# SCH_RESETDAY.net
KiCad netlist of a schematic drawn in Altium Designer
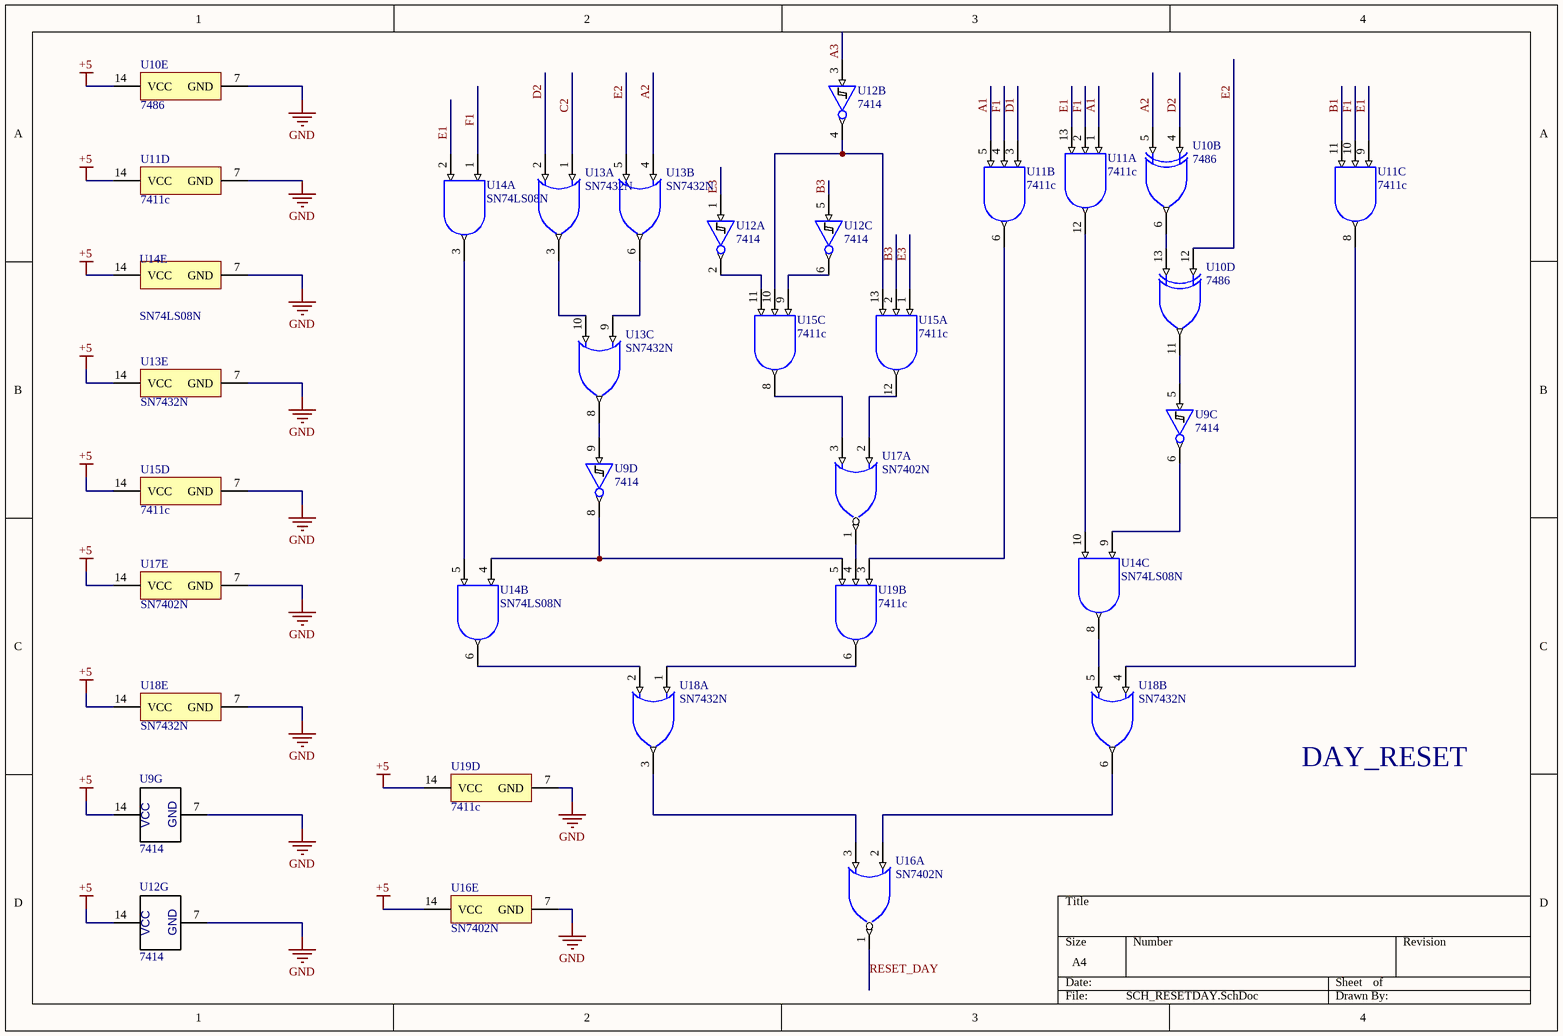
[diagram p0: SCH_RESETDAY.SchDoc]

(export (version "E")
  (design (tool "Eeschema 10.0.6"))
  (components
    (comp (ref "U9")
      (value "7414")
      (footprint "DIP14")
      (description "IC, M74HC04M, Hex Inverter, SO-14")
      (libsource (lib "") (part "7414_1"))
    )
    (comp (ref "U10")
      (value "7486")
      (footprint "N0014A")
      (description "High Speed CMOS Logic Quad 2-Input Exclusive-OR Gates, N0014A, TUBE")
      (fields
        (field (name "MANUFACTURER") "Texas Instruments")
        (field (name "GENERIC PART NUMBER") "CD74HC86")
      )
      (libsource (lib "Clock_Schlib1") (part "7486"))
    )
    (comp (ref "U11")
      (value "7411c")
      (footprint "N0014A")
      (description "High Speed CMOS Logic Triple 3-Input AND Gates, N0014A, TUBE")
      (fields
        (field (name "GENERIC PART NUMBER") "CD74HC11")
        (field (name "MANUFACTURER") "Texas Instruments")
      )
      (libsource (lib "") (part "7411c_1"))
    )
    (comp (ref "U12")
      (value "7414")
      (footprint "DIP14")
      (description "IC, M74HC04M, Hex Inverter, SO-14")
      (libsource (lib "") (part "7414_3"))
    )
    (comp (ref "U13")
      (value "SN7432N")
      (footprint "N0014A")
      (description "Quad 2-input positive-OR gates, N0014A, TUBE")
      (fields (field (name "MANUFACTURER") "Texas Instruments") (field (name "GENERIC PART NUMBER") "SN7432"))
      (libsource (lib "Altium Content Vault") (part "TI-OR-4-2IN-14"))
    )
    (comp (ref "U14")
      (value "SN74LS08N")
      (footprint "N0014A")
      (description "Quadruple 2-Input Positive-AND Gates, N0014A, TUBE")
      (fields
        (field (name "MANUFACTURER") "Texas Instruments")
        (field (name "GENERIC PART NUMBER") "SN74LS08")
      )
      (libsource (lib "") (part "TI-AND-4-2IN-14_1"))
    )
    (comp (ref "U15")
      (value "7411c")
      (footprint "N0014A")
      (description "High Speed CMOS Logic Triple 3-Input AND Gates, N0014A, TUBE")
      (fields
        (field (name "GENERIC PART NUMBER") "CD74HC11")
        (field (name "MANUFACTURER") "Texas Instruments")
      )
      (libsource (lib "Clock_Schlib1") (part "7411c"))
    )
    (comp (ref "U16")
      (value "SN7402N")
      (footprint "N0014A")
      (description "Quad 2-input Positive-NOR gates, N0014A, TUBE")
      (fields (field (name "GENERIC PART NUMBER") "SN7402") (field (name "MANUFACTURER") "Texas Instruments"))
      (libsource (lib "") (part "TI-NOR-4-2IN-14_1"))
    )
    (comp (ref "U17")
      (value "SN7402N")
      (footprint "N0014A")
      (description "Quad 2-input Positive-NOR gates, N0014A, TUBE")
      (fields (field (name "GENERIC PART NUMBER") "SN7402") (field (name "MANUFACTURER") "Texas Instruments"))
      (libsource (lib "Altium Content Vault") (part "TI-NOR-4-2IN-14"))
    )
    (comp (ref "U18")
      (value "SN7432N")
      (footprint "N0014A")
      (description "Quad 2-input positive-OR gates, N0014A, TUBE")
      (fields (field (name "MANUFACTURER") "Texas Instruments") (field (name "GENERIC PART NUMBER") "SN7432"))
      (libsource (lib "") (part "TI-OR-4-2IN-14_1"))
    )
    (comp (ref "U19")
      (value "7411c")
      (footprint "N0014A")
      (description "High Speed CMOS Logic Triple 3-Input AND Gates, N0014A, TUBE")
      (fields
        (field (name "GENERIC PART NUMBER") "CD74HC11")
        (field (name "MANUFACTURER") "Texas Instruments")
      )
      (libsource (lib "Clock_Schlib1") (part "7411c"))
    )
  )
  (nets
    (net (code "1") (name "+5") (class "Default")
      (node (ref "U10") (pin "14") (pinfunction "VCC_14") (pintype "power_in"))
      (node (ref "U11") (pin "14") (pinfunction "VCC_14") (pintype "power_in"))
      (node (ref "U12") (pin "14") (pinfunction "VCC_14") (pintype "passive"))
      (node (ref "U13") (pin "14") (pinfunction "VCC_14") (pintype "power_in"))
      (node (ref "U14") (pin "14") (pinfunction "VCC_14") (pintype "power_in"))
      (node (ref "U15") (pin "14") (pinfunction "VCC_14") (pintype "power_in"))
      (node (ref "U16") (pin "14") (pinfunction "VCC_14") (pintype "power_in"))
      (node (ref "U17") (pin "14") (pinfunction "VCC_14") (pintype "power_in"))
      (node (ref "U18") (pin "14") (pinfunction "VCC_14") (pintype "power_in"))
      (node (ref "U19") (pin "14") (pinfunction "VCC_14") (pintype "power_in"))
      (node (ref "U9") (pin "14") (pinfunction "VCC_14") (pintype "passive"))
    )
    (net (code "2") (name "/A1") (class "Default")
      (node (ref "U11") (pin "1") (pinfunction "1A_1") (pintype "input"))
      (node (ref "U11") (pin "5") (pinfunction "2C_5") (pintype "input"))
    )
    (net (code "3") (name "/A2") (class "Default")
      (node (ref "U10") (pin "5") (pinfunction "2B_5") (pintype "input"))
      (node (ref "U13") (pin "4") (pinfunction "2A_4") (pintype "input"))
    )
    (net (code "4") (name "/A3") (class "Default")
      (node (ref "U12") (pin "3") (pinfunction "A_3") (pintype "input"))
    )
    (net (code "5") (name "/B1") (class "Default")
      (node (ref "U11") (pin "11") (pinfunction "3C_11") (pintype "input"))
    )
    (net (code "6") (name "/B3") (class "Default")
      (node (ref "U12") (pin "5") (pinfunction "A_5") (pintype "input"))
      (node (ref "U15") (pin "2") (pinfunction "1B_2") (pintype "input"))
    )
    (net (code "7") (name "/C2") (class "Default")
      (node (ref "U13") (pin "1") (pinfunction "1A_1") (pintype "input"))
    )
    (net (code "8") (name "/D1") (class "Default")
      (node (ref "U11") (pin "3") (pinfunction "2A_3") (pintype "input"))
    )
    (net (code "9") (name "/D2") (class "Default")
      (node (ref "U10") (pin "4") (pinfunction "2A_4") (pintype "input"))
      (node (ref "U13") (pin "2") (pinfunction "1B_2") (pintype "input"))
    )
    (net (code "10") (name "/E1") (class "Default")
      (node (ref "U11") (pin "13") (pinfunction "1C_13") (pintype "input"))
      (node (ref "U11") (pin "9") (pinfunction "3A_9") (pintype "input"))
      (node (ref "U14") (pin "2") (pinfunction "1B_2") (pintype "input"))
    )
    (net (code "11") (name "/E2") (class "Default")
      (node (ref "U10") (pin "12") (pinfunction "4A_12") (pintype "input"))
      (node (ref "U13") (pin "5") (pinfunction "2B_5") (pintype "input"))
    )
    (net (code "12") (name "/E3") (class "Default")
      (node (ref "U12") (pin "1") (pinfunction "A_1") (pintype "input"))
      (node (ref "U15") (pin "1") (pinfunction "1A_1") (pintype "input"))
    )
    (net (code "13") (name "/F1") (class "Default")
      (node (ref "U11") (pin "10") (pinfunction "3B_10") (pintype "input"))
      (node (ref "U11") (pin "2") (pinfunction "1B_2") (pintype "input"))
      (node (ref "U11") (pin "4") (pinfunction "2B_4") (pintype "input"))
      (node (ref "U14") (pin "1") (pinfunction "1A_1") (pintype "input"))
    )
    (net (code "14") (name "/RESET_DAY") (class "Default")
      (node (ref "U16") (pin "1") (pinfunction "1Y_1") (pintype "output"))
    )
    (net (code "15") (name "GND") (class "Default")
      (node (ref "U10") (pin "7") (pinfunction "GND_7") (pintype "power_in"))
      (node (ref "U11") (pin "7") (pinfunction "GND_7") (pintype "power_in"))
      (node (ref "U12") (pin "7") (pinfunction "GND_7") (pintype "passive"))
      (node (ref "U13") (pin "7") (pinfunction "GND_7") (pintype "power_in"))
      (node (ref "U14") (pin "7") (pinfunction "GND_7") (pintype "power_in"))
      (node (ref "U15") (pin "7") (pinfunction "GND_7") (pintype "power_in"))
      (node (ref "U16") (pin "7") (pinfunction "GND_7") (pintype "power_in"))
      (node (ref "U17") (pin "7") (pinfunction "GND_7") (pintype "power_in"))
      (node (ref "U18") (pin "7") (pinfunction "GND_7") (pintype "power_in"))
      (node (ref "U19") (pin "7") (pinfunction "GND_7") (pintype "power_in"))
      (node (ref "U9") (pin "7") (pinfunction "GND_7") (pintype "passive"))
    )
    (net (code "16") (name "Net-(U10B-2Y)") (class "Default")
      (node (ref "U10") (pin "13") (pinfunction "4B_13") (pintype "input"))
      (node (ref "U10") (pin "6") (pinfunction "2Y_6") (pintype "output"))
    )
    (net (code "17") (name "Net-(U10D-4Y)") (class "Default")
      (node (ref "U10") (pin "11") (pinfunction "4Y_11") (pintype "output"))
      (node (ref "U9") (pin "5") (pinfunction "A_5") (pintype "input"))
    )
    (net (code "18") (name "Net-(U11A-1Y)") (class "Default")
      (node (ref "U11") (pin "12") (pinfunction "1Y_12") (pintype "output"))
      (node (ref "U14") (pin "10") (pinfunction "3B_10") (pintype "input"))
    )
    (net (code "19") (name "Net-(U11B-2Y)") (class "Default")
      (node (ref "U11") (pin "6") (pinfunction "2Y_6") (pintype "output"))
      (node (ref "U19") (pin "3") (pinfunction "2A_3") (pintype "input"))
    )
    (net (code "20") (name "Net-(U11C-3Y)") (class "Default")
      (node (ref "U11") (pin "8") (pinfunction "3Y_8") (pintype "output"))
      (node (ref "U18") (pin "4") (pinfunction "2A_4") (pintype "input"))
    )
    (net (code "21") (name "Net-(U12A-Y)") (class "Default")
      (node (ref "U12") (pin "2") (pinfunction "Y_2") (pintype "output"))
      (node (ref "U15") (pin "11") (pinfunction "3C_11") (pintype "input"))
    )
    (net (code "22") (name "Net-(U12B-Y)") (class "Default")
      (node (ref "U12") (pin "4") (pinfunction "Y_4") (pintype "output"))
      (node (ref "U15") (pin "10") (pinfunction "3B_10") (pintype "input"))
      (node (ref "U15") (pin "13") (pinfunction "1C_13") (pintype "input"))
    )
    (net (code "23") (name "Net-(U12C-Y)") (class "Default")
      (node (ref "U12") (pin "6") (pinfunction "Y_6") (pintype "output"))
      (node (ref "U15") (pin "9") (pinfunction "3A_9") (pintype "input"))
    )
    (net (code "24") (name "Net-(U13A-1Y)") (class "Default")
      (node (ref "U13") (pin "10") (pinfunction "3B_10") (pintype "input"))
      (node (ref "U13") (pin "3") (pinfunction "1Y_3") (pintype "output"))
    )
    (net (code "25") (name "Net-(U13B-2Y)") (class "Default")
      (node (ref "U13") (pin "6") (pinfunction "2Y_6") (pintype "output"))
      (node (ref "U13") (pin "9") (pinfunction "3A_9") (pintype "input"))
    )
    (net (code "26") (name "Net-(U13C-3Y)") (class "Default")
      (node (ref "U13") (pin "8") (pinfunction "3Y_8") (pintype "output"))
      (node (ref "U9") (pin "9") (pinfunction "A_9") (pintype "input"))
    )
    (net (code "27") (name "Net-(U14A-1Y)") (class "Default")
      (node (ref "U14") (pin "3") (pinfunction "1Y_3") (pintype "output"))
      (node (ref "U14") (pin "5") (pinfunction "2B_5") (pintype "input"))
    )
    (net (code "28") (name "Net-(U14B-2A)") (class "Default")
      (node (ref "U14") (pin "4") (pinfunction "2A_4") (pintype "input"))
      (node (ref "U19") (pin "5") (pinfunction "2C_5") (pintype "input"))
      (node (ref "U9") (pin "8") (pinfunction "Y_8") (pintype "output"))
    )
    (net (code "29") (name "Net-(U14B-2Y)") (class "Default")
      (node (ref "U14") (pin "6") (pinfunction "2Y_6") (pintype "output"))
      (node (ref "U18") (pin "2") (pinfunction "1B_2") (pintype "input"))
    )
    (net (code "30") (name "Net-(U14C-3A)") (class "Default")
      (node (ref "U14") (pin "9") (pinfunction "3A_9") (pintype "input"))
      (node (ref "U9") (pin "6") (pinfunction "Y_6") (pintype "output"))
    )
    (net (code "31") (name "Net-(U14C-3Y)") (class "Default")
      (node (ref "U14") (pin "8") (pinfunction "3Y_8") (pintype "output"))
      (node (ref "U18") (pin "5") (pinfunction "2B_5") (pintype "input"))
    )
    (net (code "32") (name "Net-(U15A-1Y)") (class "Default")
      (node (ref "U15") (pin "12") (pinfunction "1Y_12") (pintype "output"))
      (node (ref "U17") (pin "2") (pinfunction "1A_2") (pintype "input"))
    )
    (net (code "33") (name "Net-(U15C-3Y)") (class "Default")
      (node (ref "U15") (pin "8") (pinfunction "3Y_8") (pintype "output"))
      (node (ref "U17") (pin "3") (pinfunction "1B_3") (pintype "input"))
    )
    (net (code "34") (name "Net-(U16A-1A)") (class "Default")
      (node (ref "U16") (pin "2") (pinfunction "1A_2") (pintype "input"))
      (node (ref "U18") (pin "6") (pinfunction "2Y_6") (pintype "output"))
    )
    (net (code "35") (name "Net-(U16A-1B)") (class "Default")
      (node (ref "U16") (pin "3") (pinfunction "1B_3") (pintype "input"))
      (node (ref "U18") (pin "3") (pinfunction "1Y_3") (pintype "output"))
    )
    (net (code "36") (name "Net-(U17A-1Y)") (class "Default")
      (node (ref "U17") (pin "1") (pinfunction "1Y_1") (pintype "output"))
      (node (ref "U19") (pin "4") (pinfunction "2B_4") (pintype "input"))
    )
    (net (code "37") (name "Net-(U18A-1A)") (class "Default")
      (node (ref "U18") (pin "1") (pinfunction "1A_1") (pintype "input"))
      (node (ref "U19") (pin "6") (pinfunction "2Y_6") (pintype "output"))
    )
  )
)
